# D1_Breakout_-_LCD_TH_Screws.net
KiCad netlist of a schematic drawn in EAGLE
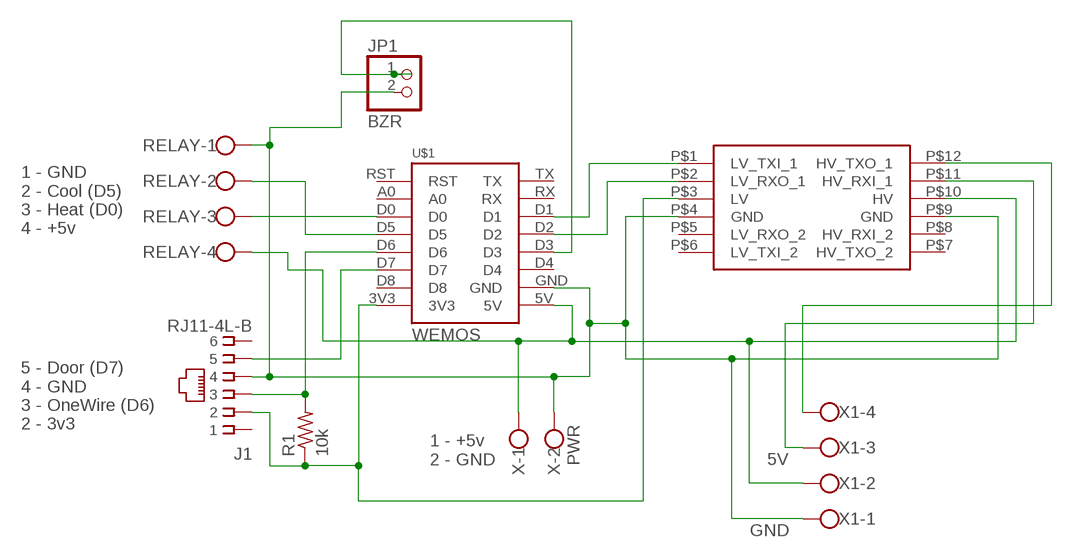
[diagram p0: schematic, sheet 1]

(export (version "E")
  (design (tool "Eeschema 10.0.6"))
  (components
    (comp (ref "J1")
      (value "RJ11-4L-B")
      (footprint "eagle-import:RJ11-NO_SHIELD")
      (fields (field (name "MF") "TYCO ELECTRONICS"))
      (libsource (lib "eagle-import") (part "RJ11-4L-B"))
    )
    (comp (ref "JP1")
      (value "BZR")
      (footprint "eagle-import:1X02")
      (libsource (lib "eagle-import") (part "PINHD-1X2"))
    )
    (comp (ref "R1")
      (value "10k")
      (footprint "eagle-import:0207_5V")
      (libsource (lib "eagle-import") (part "R-US_0207/5V"))
    )
    (comp (ref "RELAY")
      (value "W237-4")
      (footprint "eagle-import:W237-4")
      (libsource (lib "eagle-import") (part "W237-4"))
    )
    (comp (ref "U$1")
      (value "WEMOS")
      (footprint "eagle-import:WEMOS")
      (libsource (lib "eagle-import") (part "WEMOS"))
    )
    (comp (ref "U$3")
      (value "LOGIC_LEVEL_CONVERTER")
      (footprint "eagle-import:LOGIC_LEVEL_CONVERTER")
      (libsource (lib "eagle-import") (part "LOGIC_LEVEL_CONVERTER"))
    )
    (comp (ref "X")
      (value "PWR")
      (footprint "eagle-import:W237-102")
      (fields (field (name "MPN") "237-102"))
      (libsource (lib "eagle-import") (part "W237-102"))
    )
    (comp (ref "X1")
      (value "W237-4")
      (footprint "eagle-import:W237-4")
      (libsource (lib "eagle-import") (part "W237-4"))
    )
  )
  (nets
    (net (code "1") (name "/5V") (class "Default")
      (node (ref "RELAY") (pin "4") (pinfunction "KL_4") (pintype "passive"))
      (node (ref "U$1") (pin "5V") (pinfunction "5V_5V") (pintype "bidirectional"))
      (node (ref "U$3") (pin "P$10") (pinfunction "HV_P$10") (pintype "bidirectional"))
      (node (ref "X") (pin "1") (pinfunction "KL_1") (pintype "passive"))
      (node (ref "X1") (pin "2") (pinfunction "KL_2") (pintype "passive"))
    )
    (net (code "2") (name "/GND") (class "Default")
      (node (ref "J1") (pin "4") (pinfunction "4_4") (pintype "passive"))
      (node (ref "JP1") (pin "2") (pinfunction "2_2") (pintype "passive"))
      (node (ref "RELAY") (pin "1") (pinfunction "KL_1") (pintype "passive"))
      (node (ref "U$1") (pin "GND") (pinfunction "GND_GND") (pintype "bidirectional"))
      (node (ref "U$3") (pin "P$4") (pinfunction "GND_P$4") (pintype "bidirectional"))
      (node (ref "U$3") (pin "P$9") (pinfunction "GND_P$9") (pintype "bidirectional"))
      (node (ref "X") (pin "2") (pinfunction "KL_2") (pintype "passive"))
      (node (ref "X1") (pin "1") (pinfunction "KL_1") (pintype "passive"))
    )
    (net (code "3") (name "Net-(J1-Pad3)") (class "Default")
      (node (ref "J1") (pin "3") (pinfunction "3_3") (pintype "passive"))
      (node (ref "R1") (pin "2") (pinfunction "2_2") (pintype "passive"))
      (node (ref "U$1") (pin "D6") (pinfunction "D6_D6") (pintype "bidirectional"))
    )
    (net (code "4") (name "Net-(J1-Pad5)") (class "Default")
      (node (ref "J1") (pin "5") (pinfunction "5_5") (pintype "passive"))
      (node (ref "U$1") (pin "D7") (pinfunction "D7_D7") (pintype "bidirectional"))
    )
    (net (code "5") (name "Net-(JP1-Pad1)") (class "Default")
      (node (ref "JP1") (pin "1") (pinfunction "1_1") (pintype "passive"))
      (node (ref "U$1") (pin "D3") (pinfunction "D3_D3") (pintype "bidirectional"))
    )
    (net (code "6") (name "Net-(RELAYB-KL)") (class "Default")
      (node (ref "RELAY") (pin "2") (pinfunction "KL_2") (pintype "passive"))
      (node (ref "U$1") (pin "D5") (pinfunction "D5_D5") (pintype "bidirectional"))
    )
    (net (code "7") (name "Net-(RELAYC-KL)") (class "Default")
      (node (ref "RELAY") (pin "3") (pinfunction "KL_3") (pintype "passive"))
      (node (ref "U$1") (pin "D0") (pinfunction "D0_D0") (pintype "bidirectional"))
    )
    (net (code "8") (name "Net-(U$3-HV_RXI_1)") (class "Default")
      (node (ref "U$3") (pin "P$11") (pinfunction "HV_RXI_1_P$11") (pintype "bidirectional"))
      (node (ref "X1") (pin "3") (pinfunction "KL_3") (pintype "passive"))
    )
    (net (code "9") (name "Net-(U$3-HV_TXO_1)") (class "Default")
      (node (ref "U$3") (pin "P$12") (pinfunction "HV_TXO_1_P$12") (pintype "bidirectional"))
      (node (ref "X1") (pin "4") (pinfunction "KL_4") (pintype "passive"))
    )
    (net (code "10") (name "Net-(U$3-LV)") (class "Default")
      (node (ref "J1") (pin "2") (pinfunction "2_2") (pintype "passive"))
      (node (ref "R1") (pin "1") (pinfunction "1_1") (pintype "passive"))
      (node (ref "U$1") (pin "3V3") (pinfunction "3V3_3V3") (pintype "bidirectional"))
      (node (ref "U$3") (pin "P$3") (pinfunction "LV_P$3") (pintype "bidirectional"))
    )
    (net (code "11") (name "Net-(U$3-LV_RXO_1)") (class "Default")
      (node (ref "U$1") (pin "D2") (pinfunction "D2_D2") (pintype "bidirectional"))
      (node (ref "U$3") (pin "P$2") (pinfunction "LV_RXO_1_P$2") (pintype "bidirectional"))
    )
    (net (code "12") (name "Net-(U$3-LV_TXI_1)") (class "Default")
      (node (ref "U$1") (pin "D1") (pinfunction "D1_D1") (pintype "bidirectional"))
      (node (ref "U$3") (pin "P$1") (pinfunction "LV_TXI_1_P$1") (pintype "bidirectional"))
    )
    (net (code "13") (name "unconnected-(J1-Pad1)") (class "Default")
      (node (ref "J1") (pin "1") (pinfunction "1_1") (pintype "passive"))
    )
    (net (code "14") (name "unconnected-(J1-Pad6)") (class "Default")
      (node (ref "J1") (pin "6") (pinfunction "6_6") (pintype "passive"))
    )
    (net (code "15") (name "unconnected-(U$1-PadA0)") (class "Default")
      (node (ref "U$1") (pin "A0") (pinfunction "A0_A0") (pintype "bidirectional"))
    )
    (net (code "16") (name "unconnected-(U$1-PadD4)") (class "Default")
      (node (ref "U$1") (pin "D4") (pinfunction "D4_D4") (pintype "bidirectional"))
    )
    (net (code "17") (name "unconnected-(U$1-PadD8)") (class "Default")
      (node (ref "U$1") (pin "D8") (pinfunction "D8_D8") (pintype "bidirectional"))
    )
    (net (code "18") (name "unconnected-(U$1-PadRST)") (class "Default")
      (node (ref "U$1") (pin "RST") (pinfunction "RST_RST") (pintype "bidirectional"))
    )
    (net (code "19") (name "unconnected-(U$1-PadRX)") (class "Default")
      (node (ref "U$1") (pin "RX") (pinfunction "RX_RX") (pintype "bidirectional"))
    )
    (net (code "20") (name "unconnected-(U$1-PadTX)") (class "Default")
      (node (ref "U$1") (pin "TX") (pinfunction "TX_TX") (pintype "bidirectional"))
    )
    (net (code "21") (name "unconnected-(U$3-HV_RXI_2-PadP$8)") (class "Default")
      (node (ref "U$3") (pin "P$8") (pinfunction "HV_RXI_2_P$8") (pintype "bidirectional"))
    )
    (net (code "22") (name "unconnected-(U$3-HV_TXO_2-PadP$7)") (class "Default")
      (node (ref "U$3") (pin "P$7") (pinfunction "HV_TXO_2_P$7") (pintype "bidirectional"))
    )
    (net (code "23") (name "unconnected-(U$3-LV_RXO_2-PadP$5)") (class "Default")
      (node (ref "U$3") (pin "P$5") (pinfunction "LV_RXO_2_P$5") (pintype "bidirectional"))
    )
    (net (code "24") (name "unconnected-(U$3-LV_TXI_2-PadP$6)") (class "Default")
      (node (ref "U$3") (pin "P$6") (pinfunction "LV_TXI_2_P$6") (pintype "bidirectional"))
    )
  )
)
